# main.net
KiCad netlist of a schematic drawn in Altium Designer
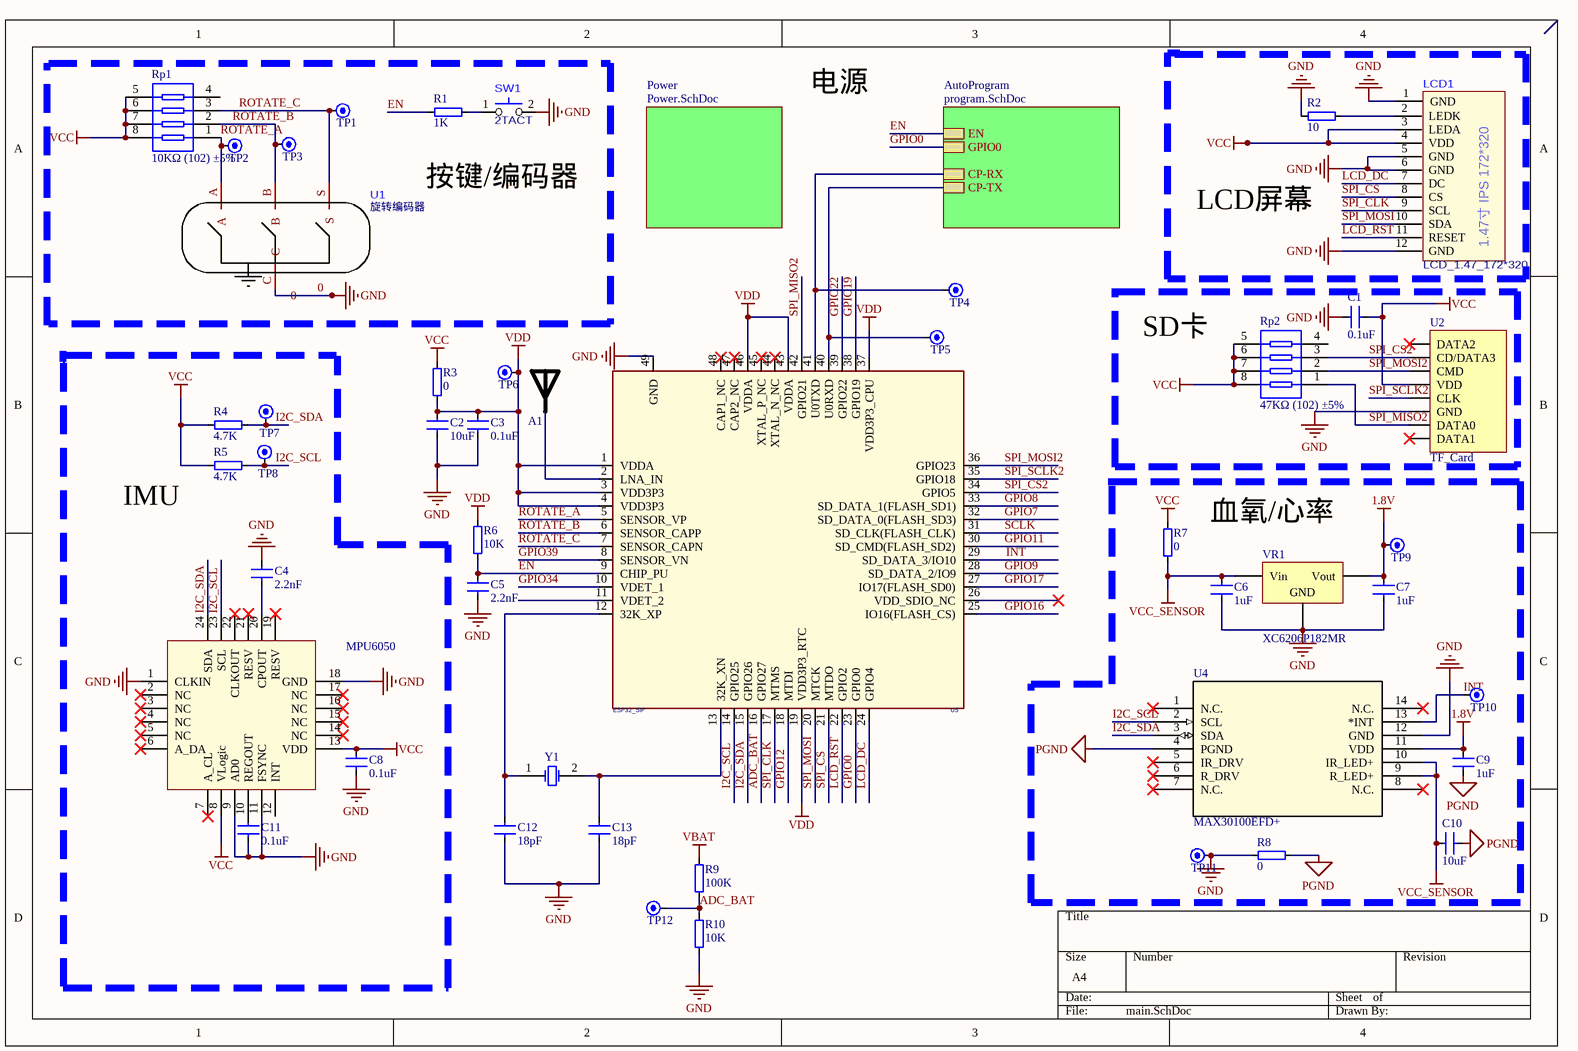
[diagram p0: main.SchDoc]

(export (version "E")
  (design (tool "Eeschema 10.0.6"))
  (components
    (comp (ref "A1")
      (value "RAINSUN")
      (footprint "ANT-Rainsun-AN5120")
      (libsource (lib "M-WatchSchlib1") (part "ANT-Rainsun-AP5120"))
    )
    (comp (ref "C1")
      (value "0.1uF")
      (footprint "C0402")
      (description "cap")
      (libsource (lib "Mylib") (part "CAP"))
    )
    (comp (ref "C2")
      (value "10uF")
      (footprint "C0402")
      (description "cap")
      (libsource (lib "Mylib") (part "CAP"))
    )
    (comp (ref "C3")
      (value "0.1uF")
      (footprint "C0402")
      (description "cap")
      (libsource (lib "Mylib") (part "CAP"))
    )
    (comp (ref "C4")
      (value "2.2nF")
      (footprint "C0402")
      (description "cap")
      (libsource (lib "Mylib") (part "CAP"))
    )
    (comp (ref "C5")
      (value "2.2nF")
      (footprint "C0402")
      (description "cap")
      (libsource (lib "Mylib") (part "CAP"))
    )
    (comp (ref "C6")
      (value "1uF")
      (footprint "C0402")
      (description "cap")
      (libsource (lib "Mylib") (part "CAP"))
    )
    (comp (ref "C7")
      (value "1uF")
      (footprint "C0402")
      (description "cap")
      (libsource (lib "Mylib") (part "CAP"))
    )
    (comp (ref "C8")
      (value "0.1uF")
      (footprint "C0402")
      (description "cap")
      (libsource (lib "Mylib") (part "CAP"))
    )
    (comp (ref "C9")
      (value "1uF")
      (footprint "C0402")
      (description "cap")
      (libsource (lib "Mylib") (part "CAP"))
    )
    (comp (ref "C10")
      (value "10uF")
      (footprint "C0402")
      (description "cap")
      (libsource (lib "Mylib") (part "CAP"))
    )
    (comp (ref "C11")
      (value "0.1uF")
      (footprint "C0402")
      (description "cap")
      (libsource (lib "Mylib") (part "CAP"))
    )
    (comp (ref "C12")
      (value "18pF")
      (footprint "C0402")
      (description "cap")
      (libsource (lib "Mylib") (part "CAP"))
    )
    (comp (ref "C13")
      (value "18pF")
      (footprint "C0402")
      (description "cap")
      (libsource (lib "Mylib") (part "CAP"))
    )
    (comp (ref "LCD1")
      (value "LCD_1.47_172*320")
      (footprint "LCD_1.47_172*320_TOP")
      (libsource (lib "M-WatchSchlib1") (part "LCD_1.47_172*320"))
    )
    (comp (ref "R1") (value "1K") (footprint "R0402") (libsource (lib "Mylib") (part "RES")))
    (comp (ref "R2") (value "10") (footprint "R0402") (libsource (lib "Mylib") (part "RES")))
    (comp (ref "R3") (value "0") (footprint "R0402") (libsource (lib "Mylib") (part "RES")))
    (comp (ref "R4") (value "4.7K") (footprint "R0402") (libsource (lib "Mylib") (part "RES")))
    (comp (ref "R5") (value "4.7K") (footprint "R0402") (libsource (lib "Mylib") (part "RES")))
    (comp (ref "R6") (value "10K") (footprint "R0402") (libsource (lib "Mylib") (part "RES")))
    (comp (ref "R7") (value "0") (footprint "R0402") (libsource (lib "Mylib") (part "RES")))
    (comp (ref "R8") (value "0") (footprint "R0402") (libsource (lib "Mylib") (part "RES")))
    (comp (ref "R9") (value "100K") (footprint "R0402") (libsource (lib "Mylib") (part "RES")))
    (comp (ref "R10") (value "10K") (footprint "R0402") (libsource (lib "Mylib") (part "RES")))
    (comp (ref "Rp1")
      (value "10KΩ (102) ±5%")
      (footprint "0402_Rx4")
      (description "贴片排阻")
      (libsource (lib "Miscellaneous Devices LC") (part "0402*4 1KΩ (102) 5%"))
    )
    (comp (ref "Rp2")
      (value "47KΩ (102) ±5%")
      (footprint "0402_Rx4")
      (description "贴片排阻")
      (libsource (lib "Miscellaneous Devices LC") (part "0402*4 1KΩ (102) 5%"))
    )
    (comp (ref "SW1")
      (value "2TACT")
      (footprint "SW-SMD_L3.9-W2.9-LS4.8-EH-A")
      (libsource (lib "M-WatchSchlib1") (part "YD-3410"))
    )
    (comp (ref "TP1") (value "TP") (footprint "Test-Point") (libsource (lib "Mylib") (part "TP")))
    (comp (ref "TP2") (value "TP") (footprint "Test-Point") (libsource (lib "Mylib") (part "TP")))
    (comp (ref "TP3") (value "TP") (footprint "Test-Point") (libsource (lib "Mylib") (part "TP")))
    (comp (ref "TP4") (value "TP") (footprint "Test-Point") (libsource (lib "Mylib") (part "TP")))
    (comp (ref "TP5") (value "TP") (footprint "Test-Point") (libsource (lib "Mylib") (part "TP")))
    (comp (ref "TP6") (value "TP") (footprint "Test-Point") (libsource (lib "Mylib") (part "TP")))
    (comp (ref "TP7") (value "TP") (footprint "Test-Point") (libsource (lib "Mylib") (part "TP")))
    (comp (ref "TP8") (value "TP") (footprint "Test-Point") (libsource (lib "Mylib") (part "TP")))
    (comp (ref "TP9") (value "TP") (footprint "Test-Point") (libsource (lib "Mylib") (part "TP")))
    (comp (ref "TP10") (value "TP") (footprint "Test-Point") (libsource (lib "Mylib") (part "TP")))
    (comp (ref "TP11") (value "TP") (footprint "Test-Point") (libsource (lib "Mylib") (part "TP")))
    (comp (ref "TP12") (value "TP") (footprint "Test-Point") (libsource (lib "Mylib") (part "TP")))
    (comp (ref "U1")
      (value "旋转编码器")
      (footprint "SW-SMD_SIQ-02FVS3_1")
      (libsource (lib "M-WatchSchlib1") (part "SIQ-02FVS3_1"))
    )
    (comp (ref "U2")
      (value "TF_Card")
      (footprint "TF_CARD_MINI")
      (libsource (lib "M-WatchSchlib1") (part "TF_Card"))
    )
    (comp (ref "U3")
      (value "MPU6050")
      (footprint "QFN-24")
      (description "六轴传感器")
      (libsource (lib "M-WatchSchlib1") (part "MPU6050"))
    )
    (comp (ref "U4")
      (value "MAX30100EFD+")
      (footprint "21-0880B_MXM")
      (description "No Description Available")
      (fields (field (name "COPYRIGHT") "Copyright (C) 2022 Ultra Librarian. All rights reserved."))
      (libsource (lib "M-WatchSchlib1") (part "MAX30100EFD+"))
    )
    (comp (ref "U5")
      (value "ESP32_SIP")
      (footprint "QFN-48_7X7")
      (libsource (lib "M-WatchSchlib1") (part "ESP32-PICO"))
    )
    (comp (ref "VR1")
      (value "XC6206P182MR")
      (footprint "SOT-23-3L")
      (description "低压差线性稳压(LDO)")
      (libsource (lib "Miscellaneous Devices LC") (part "SOT-23 XC6206P332MR"))
    )
    (comp (ref "Y1")
      (value "32.768KHz ±20ppm 12.5pF")
      (footprint "SMD-3215_2P FC - 135")
      (description "贴片晶振")
      (libsource (lib "Miscellaneous Devices LC") (part "SMD-3215_2P 32.768KHz 20ppm 12.5pF"))
    )
  )
  (nets
    (net (code "1") (name "/ADC_BAT") (class "Default")
      (node (ref "R10") (pin "1") (pinfunction "1_1") (pintype "passive"))
      (node (ref "R9") (pin "2") (pinfunction "2_2") (pintype "passive"))
      (node (ref "TP12") (pin "1") (pinfunction "Test_Point_1") (pintype "passive"))
      (node (ref "U5") (pin "16") (pinfunction "GPIO27_16") (pintype "passive"))
    )
    (net (code "2") (name "/CP-RX") (class "Default")
      (node (ref "TP4") (pin "1") (pinfunction "Test_Point_1") (pintype "passive"))
      (node (ref "U5") (pin "41") (pinfunction "U0TXD_41") (pintype "power_in"))
    )
    (net (code "3") (name "/CP-TX") (class "Default")
      (node (ref "TP5") (pin "1") (pinfunction "Test_Point_1") (pintype "passive"))
      (node (ref "U5") (pin "40") (pinfunction "U0RXD_40") (pintype "power_in"))
    )
    (net (code "4") (name "/EN") (class "Default")
      (node (ref "C5") (pin "1") (pinfunction "1_1") (pintype "passive"))
      (node (ref "R1") (pin "2") (pinfunction "2_2") (pintype "passive"))
      (node (ref "R6") (pin "1") (pinfunction "1_1") (pintype "passive"))
      (node (ref "U5") (pin "9") (pinfunction "CHIP_PU_9") (pintype "passive"))
    )
    (net (code "5") (name "/GPIO0") (class "Default")
      (node (ref "U5") (pin "23") (pinfunction "GPIO0_23") (pintype "passive"))
    )
    (net (code "6") (name "/GPIO7") (class "Default")
      (node (ref "U5") (pin "32") (pinfunction "SD_DATA_0(FLASH_SD3)_32") (pintype "passive"))
    )
    (net (code "7") (name "/GPIO8") (class "Default")
      (node (ref "U5") (pin "33") (pinfunction "SD_DATA_1(FLASH_SD1)_33") (pintype "passive"))
    )
    (net (code "8") (name "/GPIO9") (class "Default")
      (node (ref "U5") (pin "28") (pinfunction "SD_DATA_2/IO9_28") (pintype "passive"))
    )
    (net (code "9") (name "/GPIO11") (class "Default")
      (node (ref "U5") (pin "30") (pinfunction "SD_CMD(FLASH_SD2)_30") (pintype "passive"))
    )
    (net (code "10") (name "/GPIO12") (class "Default")
      (node (ref "U5") (pin "18") (pinfunction "MTDI_18") (pintype "passive"))
    )
    (net (code "11") (name "/GPIO16") (class "Default")
      (node (ref "U5") (pin "25") (pinfunction "IO16(FLASH_CS)_25") (pintype "passive"))
    )
    (net (code "12") (name "/GPIO17") (class "Default")
      (node (ref "U5") (pin "27") (pinfunction "IO17(FLASH_SD0)_27") (pintype "passive"))
    )
    (net (code "13") (name "/GPIO19") (class "Default")
      (node (ref "U5") (pin "38") (pinfunction "GPIO19_38") (pintype "passive"))
    )
    (net (code "14") (name "/GPIO22") (class "Default")
      (node (ref "U5") (pin "39") (pinfunction "GPIO22_39") (pintype "passive"))
    )
    (net (code "15") (name "/GPIO34") (class "Default")
      (node (ref "U5") (pin "10") (pinfunction "VDET_1_10") (pintype "passive"))
    )
    (net (code "16") (name "/GPIO39") (class "Default")
      (node (ref "U5") (pin "8") (pinfunction "SENSOR_VN_8") (pintype "passive"))
    )
    (net (code "17") (name "/I2C_SCL") (class "Default")
      (node (ref "R5") (pin "1") (pinfunction "1_1") (pintype "passive"))
      (node (ref "TP8") (pin "1") (pinfunction "Test_Point_1") (pintype "passive"))
      (node (ref "U3") (pin "23") (pinfunction "SCL_23") (pintype "passive"))
      (node (ref "U4") (pin "2") (pinfunction "SCL_2") (pintype "input"))
      (node (ref "U5") (pin "14") (pinfunction "GPIO25_14") (pintype "passive"))
    )
    (net (code "18") (name "/I2C_SDA") (class "Default")
      (node (ref "R4") (pin "1") (pinfunction "1_1") (pintype "passive"))
      (node (ref "TP7") (pin "1") (pinfunction "Test_Point_1") (pintype "passive"))
      (node (ref "U3") (pin "24") (pinfunction "SDA_24") (pintype "passive"))
      (node (ref "U4") (pin "3") (pinfunction "SDA_3") (pintype "bidirectional"))
      (node (ref "U5") (pin "15") (pinfunction "GPIO26_15") (pintype "passive"))
    )
    (net (code "19") (name "/INT") (class "Default")
      (node (ref "TP10") (pin "1") (pinfunction "Test_Point_1") (pintype "passive"))
      (node (ref "U4") (pin "13") (pinfunction "*INT_13") (pintype "passive"))
      (node (ref "U5") (pin "29") (pinfunction "SD_DATA_3/IO10_29") (pintype "passive"))
    )
    (net (code "20") (name "/LCD_DC") (class "Default")
      (node (ref "LCD1") (pin "7") (pinfunction "DC_7") (pintype "passive"))
      (node (ref "U5") (pin "24") (pinfunction "GPIO4_24") (pintype "passive"))
    )
    (net (code "21") (name "/LCD_RST") (class "Default")
      (node (ref "LCD1") (pin "11") (pinfunction "RESET_11") (pintype "passive"))
      (node (ref "U5") (pin "22") (pinfunction "GPIO2_22") (pintype "passive"))
    )
    (net (code "22") (name "/ROTATE_A") (class "Default")
      (node (ref "Rp1") (pin "1") (pinfunction "1_1") (pintype "passive"))
      (node (ref "TP2") (pin "1") (pinfunction "Test_Point_1") (pintype "passive"))
      (node (ref "U1") (pin "A") (pinfunction "A_A") (pintype "passive"))
      (node (ref "U5") (pin "5") (pinfunction "SENSOR_VP_5") (pintype "passive"))
    )
    (net (code "23") (name "/ROTATE_B") (class "Default")
      (node (ref "Rp1") (pin "2") (pinfunction "2_2") (pintype "passive"))
      (node (ref "TP3") (pin "1") (pinfunction "Test_Point_1") (pintype "passive"))
      (node (ref "U1") (pin "B") (pinfunction "B_B") (pintype "passive"))
      (node (ref "U5") (pin "6") (pinfunction "SENSOR_CAPP_6") (pintype "passive"))
    )
    (net (code "24") (name "/ROTATE_C") (class "Default")
      (node (ref "Rp1") (pin "3") (pinfunction "3_3") (pintype "passive"))
      (node (ref "TP1") (pin "1") (pinfunction "Test_Point_1") (pintype "passive"))
      (node (ref "U1") (pin "S") (pinfunction "S_S") (pintype "passive"))
      (node (ref "U5") (pin "7") (pinfunction "SENSOR_CAPN_7") (pintype "passive"))
    )
    (net (code "25") (name "/SCLK") (class "Default")
      (node (ref "U5") (pin "31") (pinfunction "SD_CLK(FLASH_CLK)_31") (pintype "passive"))
    )
    (net (code "26") (name "/SPI_CLK") (class "Default")
      (node (ref "LCD1") (pin "9") (pinfunction "SCL_9") (pintype "passive"))
      (node (ref "U5") (pin "17") (pinfunction "MTMS_17") (pintype "passive"))
    )
    (net (code "27") (name "/SPI_CS") (class "Default")
      (node (ref "LCD1") (pin "8") (pinfunction "CS_8") (pintype "passive"))
      (node (ref "U5") (pin "21") (pinfunction "MTDO_21") (pintype "passive"))
    )
    (net (code "28") (name "/SPI_CS2") (class "Default")
      (node (ref "Rp2") (pin "3") (pinfunction "3_3") (pintype "passive"))
      (node (ref "U2") (pin "2") (pinfunction "CD/DATA3_2") (pintype "passive"))
      (node (ref "U5") (pin "34") (pinfunction "GPIO5_34") (pintype "passive"))
    )
    (net (code "29") (name "/SPI_MISO2") (class "Default")
      (node (ref "Rp2") (pin "1") (pinfunction "1_1") (pintype "passive"))
      (node (ref "U2") (pin "7") (pinfunction "DATA0_7") (pintype "passive"))
      (node (ref "U5") (pin "42") (pinfunction "GPIO21_42") (pintype "passive"))
    )
    (net (code "30") (name "/SPI_MOSI") (class "Default")
      (node (ref "LCD1") (pin "10") (pinfunction "SDA_10") (pintype "passive"))
      (node (ref "U5") (pin "20") (pinfunction "MTCK_20") (pintype "passive"))
    )
    (net (code "31") (name "/SPI_MOSI2") (class "Default")
      (node (ref "Rp2") (pin "2") (pinfunction "2_2") (pintype "passive"))
      (node (ref "U2") (pin "3") (pinfunction "CMD_3") (pintype "passive"))
      (node (ref "U5") (pin "36") (pinfunction "GPIO23_36") (pintype "passive"))
    )
    (net (code "32") (name "/SPI_SCLK2") (class "Default")
      (node (ref "U2") (pin "5") (pinfunction "CLK_5") (pintype "passive"))
      (node (ref "U5") (pin "35") (pinfunction "GPIO18_35") (pintype "passive"))
    )
    (net (code "33") (name "1.8V") (class "Default")
      (node (ref "C7") (pin "1") (pinfunction "1_1") (pintype "passive"))
      (node (ref "C9") (pin "1") (pinfunction "1_1") (pintype "passive"))
      (node (ref "TP9") (pin "1") (pinfunction "Test_Point_1") (pintype "passive"))
      (node (ref "U4") (pin "11") (pinfunction "VDD_11") (pintype "power_in"))
      (node (ref "VR1") (pin "2") (pinfunction "Vout_2") (pintype "passive"))
    )
    (net (code "34") (name "GND") (class "Default")
      (node (ref "C1") (pin "2") (pinfunction "2_2") (pintype "passive"))
      (node (ref "C11") (pin "2") (pinfunction "2_2") (pintype "passive"))
      (node (ref "C12") (pin "2") (pinfunction "2_2") (pintype "passive"))
      (node (ref "C13") (pin "2") (pinfunction "2_2") (pintype "passive"))
      (node (ref "C2") (pin "2") (pinfunction "2_2") (pintype "passive"))
      (node (ref "C3") (pin "2") (pinfunction "2_2") (pintype "passive"))
      (node (ref "C4") (pin "1") (pinfunction "1_1") (pintype "passive"))
      (node (ref "C5") (pin "2") (pinfunction "2_2") (pintype "passive"))
      (node (ref "C6") (pin "2") (pinfunction "2_2") (pintype "passive"))
      (node (ref "C7") (pin "2") (pinfunction "2_2") (pintype "passive"))
      (node (ref "C8") (pin "2") (pinfunction "2_2") (pintype "passive"))
      (node (ref "LCD1") (pin "1") (pinfunction "GND_1") (pintype "passive"))
      (node (ref "LCD1") (pin "12") (pinfunction "GND_12") (pintype "passive"))
      (node (ref "LCD1") (pin "5") (pinfunction "GND_5") (pintype "passive"))
      (node (ref "LCD1") (pin "6") (pinfunction "GND_6") (pintype "passive"))
      (node (ref "R10") (pin "2") (pinfunction "2_2") (pintype "passive"))
      (node (ref "R2") (pin "1") (pinfunction "1_1") (pintype "passive"))
      (node (ref "R8") (pin "2") (pinfunction "2_2") (pintype "passive"))
      (node (ref "SW1") (pin "2") (pinfunction "2_2") (pintype "passive"))
      (node (ref "TP11") (pin "1") (pinfunction "Test_Point_1") (pintype "passive"))
      (node (ref "U1") (pin "0") (pinfunction "0_0") (pintype "passive"))
      (node (ref "U1") (pin "C") (pinfunction "C_C") (pintype "passive"))
      (node (ref "U2") (pin "6") (pinfunction "GND_6") (pintype "passive"))
      (node (ref "U3") (pin "1") (pinfunction "CLKIN_1") (pintype "passive"))
      (node (ref "U3") (pin "11") (pinfunction "FSYNC_11") (pintype "passive"))
      (node (ref "U3") (pin "18") (pinfunction "GND_18") (pintype "passive"))
      (node (ref "U3") (pin "9") (pinfunction "AD0_9") (pintype "passive"))
      (node (ref "U4") (pin "12") (pinfunction "GND_12") (pintype "power_in"))
      (node (ref "U5") (pin "49") (pinfunction "GND_49") (pintype "power_in"))
      (node (ref "VR1") (pin "1") (pinfunction "GND_1") (pintype "passive"))
    )
    (net (code "35") (name "Net-(LCD1-LEDK)") (class "Default")
      (node (ref "LCD1") (pin "2") (pinfunction "LEDK_2") (pintype "passive"))
      (node (ref "R2") (pin "2") (pinfunction "2_2") (pintype "passive"))
    )
    (net (code "36") (name "Net-(R1-Pad1)") (class "Default")
      (node (ref "R1") (pin "1") (pinfunction "1_1") (pintype "passive"))
      (node (ref "SW1") (pin "1") (pinfunction "1_1") (pintype "passive"))
    )
    (net (code "37") (name "Net-(U3-CPOUT)") (class "Default")
      (node (ref "C4") (pin "2") (pinfunction "2_2") (pintype "passive"))
      (node (ref "U3") (pin "20") (pinfunction "CPOUT_20") (pintype "passive"))
    )
    (net (code "38") (name "Net-(U3-REGOUT)") (class "Default")
      (node (ref "C11") (pin "1") (pinfunction "1_1") (pintype "passive"))
      (node (ref "U3") (pin "10") (pinfunction "REGOUT_10") (pintype "passive"))
    )
    (net (code "39") (name "Net-(U5-32K_XN)") (class "Default")
      (node (ref "C13") (pin "1") (pinfunction "1_1") (pintype "passive"))
      (node (ref "U5") (pin "13") (pinfunction "32K_XN_13") (pintype "passive"))
      (node (ref "Y1") (pin "2") (pinfunction "OSC2_2") (pintype "passive"))
    )
    (net (code "40") (name "Net-(U5-32K_XP)") (class "Default")
      (node (ref "C12") (pin "1") (pinfunction "1_1") (pintype "passive"))
      (node (ref "U5") (pin "12") (pinfunction "32K_XP_12") (pintype "passive"))
      (node (ref "Y1") (pin "1") (pinfunction "OSC1_1") (pintype "passive"))
    )
    (net (code "41") (name "Net-(U5-LNA_IN)") (class "Default")
      (node (ref "A1") (pin "1") (pinfunction "1_1") (pintype "passive"))
      (node (ref "U5") (pin "2") (pinfunction "LNA_IN_2") (pintype "passive"))
    )
    (net (code "42") (name "PGND") (class "Default")
      (node (ref "C10") (pin "1") (pinfunction "1_1") (pintype "passive"))
      (node (ref "C9") (pin "2") (pinfunction "2_2") (pintype "passive"))
      (node (ref "R8") (pin "1") (pinfunction "1_1") (pintype "passive"))
      (node (ref "U4") (pin "4") (pinfunction "PGND_4") (pintype "power_in"))
    )
    (net (code "43") (name "VBAT") (class "Default")
      (node (ref "R9") (pin "1") (pinfunction "1_1") (pintype "passive"))
    )
    (net (code "44") (name "VCC") (class "Default")
      (node (ref "C1") (pin "1") (pinfunction "1_1") (pintype "passive"))
      (node (ref "C8") (pin "1") (pinfunction "1_1") (pintype "passive"))
      (node (ref "LCD1") (pin "3") (pinfunction "LEDA_3") (pintype "passive"))
      (node (ref "LCD1") (pin "4") (pinfunction "VDD_4") (pintype "passive"))
      (node (ref "R3") (pin "2") (pinfunction "2_2") (pintype "passive"))
      (node (ref "R4") (pin "2") (pinfunction "2_2") (pintype "passive"))
      (node (ref "R5") (pin "2") (pinfunction "2_2") (pintype "passive"))
      (node (ref "R7") (pin "2") (pinfunction "2_2") (pintype "passive"))
      (node (ref "Rp1") (pin "5") (pinfunction "5_5") (pintype "passive"))
      (node (ref "Rp1") (pin "6") (pinfunction "6_6") (pintype "passive"))
      (node (ref "Rp1") (pin "7") (pinfunction "7_7") (pintype "passive"))
      (node (ref "Rp1") (pin "8") (pinfunction "8_8") (pintype "passive"))
      (node (ref "Rp2") (pin "5") (pinfunction "5_5") (pintype "passive"))
      (node (ref "Rp2") (pin "6") (pinfunction "6_6") (pintype "passive"))
      (node (ref "Rp2") (pin "7") (pinfunction "7_7") (pintype "passive"))
      (node (ref "Rp2") (pin "8") (pinfunction "8_8") (pintype "passive"))
      (node (ref "U2") (pin "4") (pinfunction "VDD_4") (pintype "passive"))
      (node (ref "U3") (pin "13") (pinfunction "VDD_13") (pintype "passive"))
      (node (ref "U3") (pin "8") (pinfunction "VLogic_8") (pintype "passive"))
    )
    (net (code "45") (name "VCC_SENSOR") (class "Default")
      (node (ref "C10") (pin "2") (pinfunction "2_2") (pintype "passive"))
      (node (ref "C6") (pin "1") (pinfunction "1_1") (pintype "passive"))
      (node (ref "R7") (pin "1") (pinfunction "1_1") (pintype "passive"))
      (node (ref "U4") (pin "10") (pinfunction "IR_LED+_10") (pintype "passive"))
      (node (ref "U4") (pin "9") (pinfunction "R_LED+_9") (pintype "passive"))
      (node (ref "VR1") (pin "3") (pinfunction "Vin_3") (pintype "passive"))
    )
    (net (code "46") (name "VDD") (class "Default")
      (node (ref "C2") (pin "1") (pinfunction "1_1") (pintype "passive"))
      (node (ref "C3") (pin "1") (pinfunction "1_1") (pintype "passive"))
      (node (ref "R3") (pin "1") (pinfunction "1_1") (pintype "passive"))
      (node (ref "R6") (pin "2") (pinfunction "2_2") (pintype "passive"))
      (node (ref "TP6") (pin "1") (pinfunction "Test_Point_1") (pintype "passive"))
      (node (ref "U5") (pin "1") (pinfunction "VDDA_1") (pintype "power_in"))
      (node (ref "U5") (pin "19") (pinfunction "VDD3P3_RTC_19") (pintype "power_in"))
      (node (ref "U5") (pin "3") (pinfunction "VDD3P3_3") (pintype "power_in"))
      (node (ref "U5") (pin "37") (pinfunction "VDD3P3_CPU_37") (pintype "power_in"))
      (node (ref "U5") (pin "4") (pinfunction "VDD3P3_4") (pintype "power_in"))
      (node (ref "U5") (pin "43") (pinfunction "VDDA_43") (pintype "power_in"))
      (node (ref "U5") (pin "46") (pinfunction "VDDA_46") (pintype "power_in"))
    )
    (net (code "47") (name "unconnected-(Rp1-Pad4)") (class "Default")
      (node (ref "Rp1") (pin "4") (pinfunction "4_4") (pintype "passive"))
    )
    (net (code "48") (name "unconnected-(Rp2-Pad4)") (class "Default")
      (node (ref "Rp2") (pin "4") (pinfunction "4_4") (pintype "passive"))
    )
    (net (code "49") (name "unconnected-(U2-DATA1-Pad8)") (class "Default")
      (node (ref "U2") (pin "8") (pinfunction "DATA1_8") (pintype "passive+no_connect"))
    )
    (net (code "50") (name "unconnected-(U2-DATA2-Pad1)") (class "Default")
      (node (ref "U2") (pin "1") (pinfunction "DATA2_1") (pintype "passive+no_connect"))
    )
    (net (code "51") (name "unconnected-(U3-A_CL-Pad7)") (class "Default")
      (node (ref "U3") (pin "7") (pinfunction "A_CL_7") (pintype "passive+no_connect"))
    )
    (net (code "52") (name "unconnected-(U3-A_DA-Pad6)") (class "Default")
      (node (ref "U3") (pin "6") (pinfunction "A_DA_6") (pintype "passive+no_connect"))
    )
    (net (code "53") (name "unconnected-(U3-CLKOUT-Pad22)") (class "Default")
      (node (ref "U3") (pin "22") (pinfunction "CLKOUT_22") (pintype "passive+no_connect"))
    )
    (net (code "54") (name "unconnected-(U3-INT-Pad12)") (class "Default")
      (node (ref "U3") (pin "12") (pinfunction "INT_12") (pintype "passive"))
    )
    (net (code "55") (name "unconnected-(U3-NC-Pad2)") (class "Default")
      (node (ref "U3") (pin "2") (pinfunction "NC_2") (pintype "passive+no_connect"))
    )
    (net (code "56") (name "unconnected-(U3-NC-Pad3)") (class "Default")
      (node (ref "U3") (pin "3") (pinfunction "NC_3") (pintype "passive+no_connect"))
    )
    (net (code "57") (name "unconnected-(U3-NC-Pad4)") (class "Default")
      (node (ref "U3") (pin "4") (pinfunction "NC_4") (pintype "passive+no_connect"))
    )
    (net (code "58") (name "unconnected-(U3-NC-Pad5)") (class "Default")
      (node (ref "U3") (pin "5") (pinfunction "NC_5") (pintype "passive+no_connect"))
    )
    (net (code "59") (name "unconnected-(U3-NC-Pad14)") (class "Default")
      (node (ref "U3") (pin "14") (pinfunction "NC_14") (pintype "passive+no_connect"))
    )
    (net (code "60") (name "unconnected-(U3-NC-Pad15)") (class "Default")
      (node (ref "U3") (pin "15") (pinfunction "NC_15") (pintype "passive+no_connect"))
    )
    (net (code "61") (name "unconnected-(U3-NC-Pad16)") (class "Default")
      (node (ref "U3") (pin "16") (pinfunction "NC_16") (pintype "passive+no_connect"))
    )
    (net (code "62") (name "unconnected-(U3-NC-Pad17)") (class "Default")
      (node (ref "U3") (pin "17") (pinfunction "NC_17") (pintype "passive+no_connect"))
    )
    (net (code "63") (name "unconnected-(U3-RESV-Pad19)") (class "Default")
      (node (ref "U3") (pin "19") (pinfunction "RESV_19") (pintype "passive+no_connect"))
    )
    (net (code "64") (name "unconnected-(U3-RESV-Pad21)") (class "Default")
      (node (ref "U3") (pin "21") (pinfunction "RESV_21") (pintype "passive+no_connect"))
    )
    (net (code "65") (name "unconnected-(U4-IR_DRV-Pad5)") (class "Default")
      (node (ref "U4") (pin "5") (pinfunction "IR_DRV_5") (pintype "passive+no_connect"))
    )
    (net (code "66") (name "unconnected-(U4-N.C.-Pad1)") (class "Default")
      (node (ref "U4") (pin "1") (pinfunction "N.C._1") (pintype "passive+no_connect"))
    )
    (net (code "67") (name "unconnected-(U4-N.C.-Pad7)") (class "Default")
      (node (ref "U4") (pin "7") (pinfunction "N.C._7") (pintype "passive+no_connect"))
    )
    (net (code "68") (name "unconnected-(U4-N.C.-Pad8)") (class "Default")
      (node (ref "U4") (pin "8") (pinfunction "N.C._8") (pintype "passive+no_connect"))
    )
    (net (code "69") (name "unconnected-(U4-N.C.-Pad14)") (class "Default")
      (node (ref "U4") (pin "14") (pinfunction "N.C._14") (pintype "passive+no_connect"))
    )
    (net (code "70") (name "unconnected-(U4-R_DRV-Pad6)") (class "Default")
      (node (ref "U4") (pin "6") (pinfunction "R_DRV_6") (pintype "passive+no_connect"))
    )
    (net (code "71") (name "unconnected-(U5-CAP1_NC-Pad48)") (class "Default")
      (node (ref "U5") (pin "48") (pinfunction "CAP1_NC_48") (pintype "passive+no_connect"))
    )
    (net (code "72") (name "unconnected-(U5-CAP2_NC-Pad47)") (class "Default")
      (node (ref "U5") (pin "47") (pinfunction "CAP2_NC_47") (pintype "passive+no_connect"))
    )
    (net (code "73") (name "unconnected-(U5-VDD_SDIO_NC-Pad26)") (class "Default")
      (node (ref "U5") (pin "26") (pinfunction "VDD_SDIO_NC_26") (pintype "passive+no_connect"))
    )
    (net (code "74") (name "unconnected-(U5-VDET_2-Pad11)") (class "Default")
      (node (ref "U5") (pin "11") (pinfunction "VDET_2_11") (pintype "passive"))
    )
    (net (code "75") (name "unconnected-(U5-XTAL_N_NC-Pad44)") (class "Default")
      (node (ref "U5") (pin "44") (pinfunction "XTAL_N_NC_44") (pintype "passive+no_connect"))
    )
    (net (code "76") (name "unconnected-(U5-XTAL_P_NC-Pad45)") (class "Default")
      (node (ref "U5") (pin "45") (pinfunction "XTAL_P_NC_45") (pintype "passive+no_connect"))
    )
  )
)
